# indoor-air-quality-shield.net
KiCad netlist of a schematic drawn in EAGLE
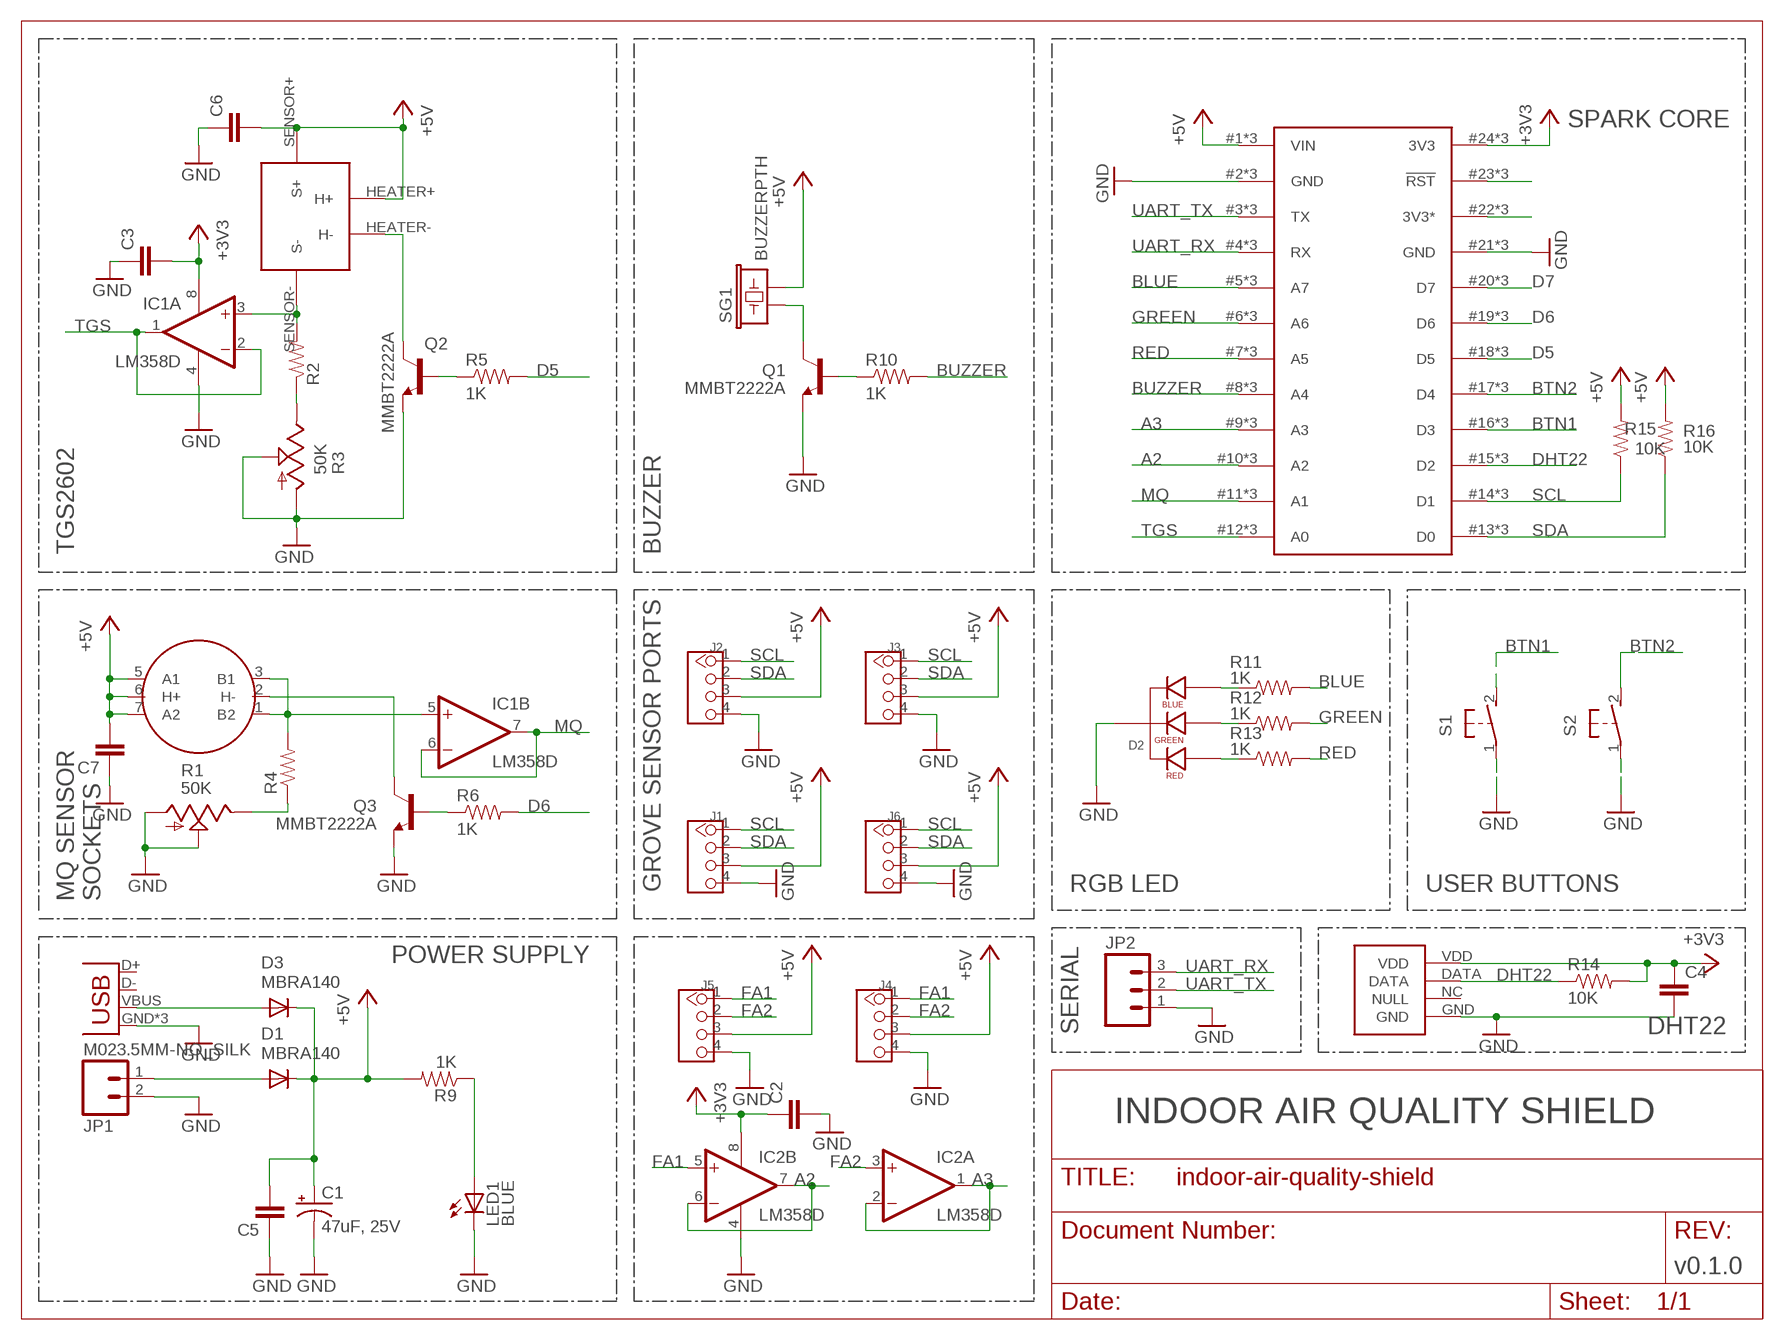
[diagram p0: schematic, sheet 1]

(export (version "E")
  (design (tool "Eeschema 10.0.6"))
  (components
    (comp (ref "C1")
      (value "47uF, 25V")
      (footprint "eagle-import:PANASONIC_D")
      (libsource (lib "eagle-import") (part "CAP_POLD"))
    )
    (comp (ref "C2")
      (value "C-EUC0603")
      (footprint "eagle-import:C0603")
      (libsource (lib "eagle-import") (part "C-EUC0603"))
    )
    (comp (ref "C3")
      (value "C-EUC0603")
      (footprint "eagle-import:C0603")
      (libsource (lib "eagle-import") (part "C-EUC0603"))
    )
    (comp (ref "C4")
      (value "C-EUC0603")
      (footprint "eagle-import:C0603")
      (libsource (lib "eagle-import") (part "C-EUC0603"))
    )
    (comp (ref "C5")
      (value "C-EUC0603")
      (footprint "eagle-import:C0603")
      (libsource (lib "eagle-import") (part "C-EUC0603"))
    )
    (comp (ref "C6")
      (value "C-EUC0603")
      (footprint "eagle-import:C0603")
      (libsource (lib "eagle-import") (part "C-EUC0603"))
    )
    (comp (ref "C7")
      (value "C-EUC0603")
      (footprint "eagle-import:C0603")
      (libsource (lib "eagle-import") (part "C-EUC0603"))
    )
    (comp (ref "D1")
      (value "MBRA140")
      (footprint "eagle-import:SMA-DIODE")
      (libsource (lib "eagle-import") (part "DIODESMA"))
    )
    (comp (ref "D2")
      (value "LED-RGB-CC-THRUCLEAR")
      (footprint "eagle-import:LED-RGB-THRU")
      (libsource (lib "eagle-import") (part "LED-RGB-CC-THRUCLEAR"))
    )
    (comp (ref "D3")
      (value "MBRA140")
      (footprint "eagle-import:SMA-DIODE")
      (libsource (lib "eagle-import") (part "DIODESMA"))
    )
    (comp (ref "IC1")
      (value "LM358D")
      (footprint "eagle-import:SO08")
      (libsource (lib "eagle-import") (part "LM358D"))
    )
    (comp (ref "IC2")
      (value "LM358D")
      (footprint "eagle-import:SO08")
      (libsource (lib "eagle-import") (part "LM358D"))
    )
    (comp (ref "J1")
      (value "TWIG-4P-2.0'D90'")
      (footprint "eagle-import:4P-2.0-90D-W_O-BUCKLE")
      (libsource (lib "eagle-import") (part "TWIG-4P-2.0'D90'"))
    )
    (comp (ref "J2")
      (value "TWIG-4P-2.0'D90'")
      (footprint "eagle-import:4P-2.0-90D-W_O-BUCKLE")
      (libsource (lib "eagle-import") (part "TWIG-4P-2.0'D90'"))
    )
    (comp (ref "J3")
      (value "TWIG-4P-2.0'D90'")
      (footprint "eagle-import:4P-2.0-90D-W_O-BUCKLE")
      (libsource (lib "eagle-import") (part "TWIG-4P-2.0'D90'"))
    )
    (comp (ref "J4")
      (value "TWIG-4P-2.0'D90'")
      (footprint "eagle-import:4P-2.0-90D-W_O-BUCKLE")
      (libsource (lib "eagle-import") (part "TWIG-4P-2.0'D90'"))
    )
    (comp (ref "J5")
      (value "TWIG-4P-2.0'D90'")
      (footprint "eagle-import:4P-2.0-90D-W_O-BUCKLE")
      (libsource (lib "eagle-import") (part "TWIG-4P-2.0'D90'"))
    )
    (comp (ref "J6")
      (value "TWIG-4P-2.0'D90'")
      (footprint "eagle-import:4P-2.0-90D-W_O-BUCKLE")
      (libsource (lib "eagle-import") (part "TWIG-4P-2.0'D90'"))
    )
    (comp (ref "JP1")
      (value "M023.5MM-NO_SILK")
      (footprint "eagle-import:SCREWTERMINAL-3.5MM-2-NS")
      (libsource (lib "eagle-import") (part "M023.5MM-NO_SILK"))
    )
    (comp (ref "JP2")
      (value "M03PTH")
      (footprint "eagle-import:1X03")
      (libsource (lib "eagle-import") (part "M03PTH"))
    )
    (comp (ref "JP3")
      (value "USBUSB-MICROB-SLOT-HOLE")
      (footprint "eagle-import:USB-MICROB-SLOT-HOLE")
      (libsource (lib "eagle-import") (part "USBUSB-MICROB-SLOT-HOLE"))
    )
    (comp (ref "LED1")
      (value "BLUE")
      (footprint "eagle-import:LED-0603")
      (libsource (lib "eagle-import") (part "LED0603"))
    )
    (comp (ref "Q1")
      (value "MMBT2222A")
      (footprint "eagle-import:SOT23-3")
      (libsource (lib "eagle-import") (part "TRANSISTOR_NPNMMBT2222A"))
    )
    (comp (ref "Q2")
      (value "MMBT2222A")
      (footprint "eagle-import:SOT23-3")
      (libsource (lib "eagle-import") (part "TRANSISTOR_NPNMMBT2222A"))
    )
    (comp (ref "Q3")
      (value "MMBT2222A")
      (footprint "eagle-import:SOT23-3")
      (libsource (lib "eagle-import") (part "TRANSISTOR_NPNMMBT2222A"))
    )
    (comp (ref "R1")
      (value "50K")
      (footprint "eagle-import:RJ9W")
      (libsource (lib "eagle-import") (part "TRIM_US-RJ9W"))
    )
    (comp (ref "R2")
      (value "RESISTOR0603")
      (footprint "eagle-import:0603-RES")
      (libsource (lib "eagle-import") (part "RESISTOR0603"))
    )
    (comp (ref "R3")
      (value "50K")
      (footprint "eagle-import:RJ9W")
      (libsource (lib "eagle-import") (part "TRIM_US-RJ9W"))
    )
    (comp (ref "R4")
      (value "RESISTOR0603")
      (footprint "eagle-import:0603-RES")
      (libsource (lib "eagle-import") (part "RESISTOR0603"))
    )
    (comp (ref "R5")
      (value "1K")
      (footprint "eagle-import:0603-RES")
      (libsource (lib "eagle-import") (part "RESISTOR0603-RES"))
    )
    (comp (ref "R6")
      (value "1K")
      (footprint "eagle-import:0603-RES")
      (libsource (lib "eagle-import") (part "RESISTOR0603-RES"))
    )
    (comp (ref "R9")
      (value "1K")
      (footprint "eagle-import:0603-RES")
      (libsource (lib "eagle-import") (part "RESISTOR0603-RES"))
    )
    (comp (ref "R10")
      (value "1K")
      (footprint "eagle-import:0603-RES")
      (libsource (lib "eagle-import") (part "RESISTOR0603-RES"))
    )
    (comp (ref "R11")
      (value "1K")
      (footprint "eagle-import:0603-RES")
      (libsource (lib "eagle-import") (part "RESISTOR0603-RES"))
    )
    (comp (ref "R12")
      (value "1K")
      (footprint "eagle-import:0603-RES")
      (libsource (lib "eagle-import") (part "RESISTOR0603-RES"))
    )
    (comp (ref "R13")
      (value "1K")
      (footprint "eagle-import:0603-RES")
      (libsource (lib "eagle-import") (part "RESISTOR0603-RES"))
    )
    (comp (ref "R14")
      (value "10K")
      (footprint "eagle-import:0603-RES")
      (libsource (lib "eagle-import") (part "RESISTOR0603-RES"))
    )
    (comp (ref "R15")
      (value "10K")
      (footprint "eagle-import:0603-RES")
      (libsource (lib "eagle-import") (part "RESISTOR0603-RES"))
    )
    (comp (ref "R16")
      (value "10K")
      (footprint "eagle-import:0603-RES")
      (libsource (lib "eagle-import") (part "RESISTOR0603-RES"))
    )
    (comp (ref "S1")
      (value "31-XX")
      (footprint "eagle-import:B3F-31XX")
      (fields (field (name "MPN") "B3F-3100"))
      (libsource (lib "eagle-import") (part "31-XX"))
    )
    (comp (ref "S2")
      (value "31-XX")
      (footprint "eagle-import:B3F-31XX")
      (fields (field (name "MPN") "B3F-3100"))
      (libsource (lib "eagle-import") (part "31-XX"))
    )
    (comp (ref "SG1")
      (value "BUZZERPTH")
      (footprint "eagle-import:BUZZER-12MM")
      (libsource (lib "eagle-import") (part "BUZZERPTH"))
    )
    (comp (ref "U$1")
      (value "TGS2602")
      (footprint "eagle-import:TGS2602")
      (libsource (lib "eagle-import") (part "TGS2602"))
    )
    (comp (ref "U$2")
      (value "MQ_SENSOR_SOCKET")
      (footprint "eagle-import:MQ_SENSOR_SOCKET")
      (libsource (lib "eagle-import") (part "MQ_SENSOR_SOCKET"))
    )
    (comp (ref "U$5")
      (value "DHT22")
      (footprint "eagle-import:DHT22")
      (libsource (lib "eagle-import") (part "DHT22"))
    )
    (comp (ref "U$6")
      (value "SPARK_CORE")
      (footprint "eagle-import:SPARK_CORE_STACKABLE")
      (libsource (lib "eagle-import") (part "SPARK_CORE"))
    )
  )
  (nets
    (net (code "1") (name "+3V3") (class "Default")
      (node (ref "C2") (pin "1") (pinfunction "1_1") (pintype "passive"))
      (node (ref "C3") (pin "2") (pinfunction "2_2") (pintype "passive"))
      (node (ref "C4") (pin "1") (pinfunction "1_1") (pintype "passive"))
      (node (ref "IC1") (pin "8") (pinfunction "V+_8") (pintype "power_in"))
      (node (ref "IC2") (pin "8") (pinfunction "V+_8") (pintype "power_in"))
      (node (ref "R14") (pin "2") (pinfunction "2_2") (pintype "passive"))
      (node (ref "U$5") (pin "VDD") (pinfunction "VDD_VDD") (pintype "power_in"))
      (node (ref "U$6") (pin "#24") (pinfunction "3V3_#24") (pintype "power_in"))
      (node (ref "U$6") (pin "24") (pinfunction "3V3_24") (pintype "power_in"))
      (node (ref "U$6") (pin "@24") (pinfunction "3V3_@24") (pintype "power_in"))
    )
    (net (code "2") (name "+5V") (class "Default")
      (node (ref "C1") (pin "+") (pinfunction "+_+") (pintype "passive"))
      (node (ref "C5") (pin "2") (pinfunction "2_2") (pintype "passive"))
      (node (ref "C6") (pin "2") (pinfunction "2_2") (pintype "passive"))
      (node (ref "C7") (pin "2") (pinfunction "2_2") (pintype "passive"))
      (node (ref "D1") (pin "C") (pinfunction "C_C") (pintype "passive"))
      (node (ref "D3") (pin "C") (pinfunction "C_C") (pintype "passive"))
      (node (ref "J1") (pin "3") (pinfunction "3_3") (pintype "bidirectional"))
      (node (ref "J2") (pin "3") (pinfunction "3_3") (pintype "bidirectional"))
      (node (ref "J3") (pin "3") (pinfunction "3_3") (pintype "bidirectional"))
      (node (ref "J4") (pin "3") (pinfunction "3_3") (pintype "bidirectional"))
      (node (ref "J5") (pin "3") (pinfunction "3_3") (pintype "bidirectional"))
      (node (ref "J6") (pin "3") (pinfunction "3_3") (pintype "bidirectional"))
      (node (ref "R15") (pin "2") (pinfunction "2_2") (pintype "passive"))
      (node (ref "R16") (pin "2") (pinfunction "2_2") (pintype "passive"))
      (node (ref "R9") (pin "2") (pinfunction "2_2") (pintype "passive"))
      (node (ref "SG1") (pin "-") (pinfunction "2_-") (pintype "passive"))
      (node (ref "U$1") (pin "HEATER+") (pinfunction "H+_HEATER+") (pintype "bidirectional"))
      (node (ref "U$1") (pin "SENSOR+") (pinfunction "S+_SENSOR+") (pintype "bidirectional"))
      (node (ref "U$2") (pin "5") (pinfunction "A1_5") (pintype "bidirectional"))
      (node (ref "U$2") (pin "6") (pinfunction "H+_6") (pintype "bidirectional"))
      (node (ref "U$2") (pin "7") (pinfunction "A2_7") (pintype "bidirectional"))
      (node (ref "U$6") (pin "#1") (pinfunction "VIN_#1") (pintype "power_in"))
      (node (ref "U$6") (pin "1") (pinfunction "VIN_1") (pintype "power_in"))
      (node (ref "U$6") (pin "@1") (pinfunction "VIN_@1") (pintype "power_in"))
    )
    (net (code "3") (name "/A2") (class "Default")
      (node (ref "IC2") (pin "6") (pinfunction "-IN_6") (pintype "input"))
      (node (ref "IC2") (pin "7") (pinfunction "OUT_7") (pintype "output"))
      (node (ref "U$6") (pin "#10") (pinfunction "A2_#10") (pintype "bidirectional"))
      (node (ref "U$6") (pin "10") (pinfunction "A2_10") (pintype "bidirectional"))
      (node (ref "U$6") (pin "@10") (pinfunction "A2_@10") (pintype "bidirectional"))
    )
    (net (code "4") (name "/A3") (class "Default")
      (node (ref "IC2") (pin "1") (pinfunction "OUT_1") (pintype "output"))
      (node (ref "IC2") (pin "2") (pinfunction "-IN_2") (pintype "input"))
      (node (ref "U$6") (pin "#9") (pinfunction "A3_#9") (pintype "bidirectional"))
      (node (ref "U$6") (pin "9") (pinfunction "A3_9") (pintype "bidirectional"))
      (node (ref "U$6") (pin "@9") (pinfunction "A3_@9") (pintype "bidirectional"))
    )
    (net (code "5") (name "/BLUE") (class "Default")
      (node (ref "R11") (pin "2") (pinfunction "2_2") (pintype "passive"))
      (node (ref "U$6") (pin "#5") (pinfunction "A7_#5") (pintype "bidirectional"))
      (node (ref "U$6") (pin "5") (pinfunction "A7_5") (pintype "bidirectional"))
      (node (ref "U$6") (pin "@5") (pinfunction "A7_@5") (pintype "bidirectional"))
    )
    (net (code "6") (name "/BTN1") (class "Default")
      (node (ref "S1") (pin "2") (pinfunction "S_2") (pintype "passive"))
      (node (ref "U$6") (pin "#16") (pinfunction "D3_#16") (pintype "bidirectional"))
      (node (ref "U$6") (pin "16") (pinfunction "D3_16") (pintype "bidirectional"))
      (node (ref "U$6") (pin "@16") (pinfunction "D3_@16") (pintype "bidirectional"))
    )
    (net (code "7") (name "/BTN2") (class "Default")
      (node (ref "S2") (pin "2") (pinfunction "S_2") (pintype "passive"))
      (node (ref "U$6") (pin "#17") (pinfunction "D4_#17") (pintype "bidirectional"))
      (node (ref "U$6") (pin "17") (pinfunction "D4_17") (pintype "bidirectional"))
      (node (ref "U$6") (pin "@17") (pinfunction "D4_@17") (pintype "bidirectional"))
    )
    (net (code "8") (name "/BUZZER") (class "Default")
      (node (ref "R10") (pin "2") (pinfunction "2_2") (pintype "passive"))
      (node (ref "U$6") (pin "#8") (pinfunction "A4_#8") (pintype "bidirectional"))
      (node (ref "U$6") (pin "8") (pinfunction "A4_8") (pintype "bidirectional"))
      (node (ref "U$6") (pin "@8") (pinfunction "A4_@8") (pintype "bidirectional"))
    )
    (net (code "9") (name "/D5") (class "Default")
      (node (ref "R5") (pin "2") (pinfunction "2_2") (pintype "passive"))
      (node (ref "U$6") (pin "#18") (pinfunction "D5_#18") (pintype "bidirectional"))
      (node (ref "U$6") (pin "18") (pinfunction "D5_18") (pintype "bidirectional"))
      (node (ref "U$6") (pin "@18") (pinfunction "D5_@18") (pintype "bidirectional"))
    )
    (net (code "10") (name "/D6") (class "Default")
      (node (ref "R6") (pin "2") (pinfunction "2_2") (pintype "passive"))
      (node (ref "U$6") (pin "#19") (pinfunction "D6_#19") (pintype "bidirectional"))
      (node (ref "U$6") (pin "19") (pinfunction "D6_19") (pintype "bidirectional"))
      (node (ref "U$6") (pin "@19") (pinfunction "D6_@19") (pintype "bidirectional"))
    )
    (net (code "11") (name "/D7") (class "Default")
      (node (ref "U$6") (pin "#20") (pinfunction "D7_#20") (pintype "bidirectional"))
      (node (ref "U$6") (pin "20") (pinfunction "D7_20") (pintype "bidirectional"))
      (node (ref "U$6") (pin "@20") (pinfunction "D7_@20") (pintype "bidirectional"))
    )
    (net (code "12") (name "/DHT22") (class "Default")
      (node (ref "R14") (pin "1") (pinfunction "1_1") (pintype "passive"))
      (node (ref "U$5") (pin "DATA") (pinfunction "DATA_DATA") (pintype "output"))
      (node (ref "U$6") (pin "#15") (pinfunction "D2_#15") (pintype "bidirectional"))
      (node (ref "U$6") (pin "15") (pinfunction "D2_15") (pintype "bidirectional"))
      (node (ref "U$6") (pin "@15") (pinfunction "D2_@15") (pintype "bidirectional"))
    )
    (net (code "13") (name "/FA1") (class "Default")
      (node (ref "IC2") (pin "5") (pinfunction "+IN_5") (pintype "input"))
      (node (ref "J4") (pin "1") (pinfunction "1_1") (pintype "bidirectional"))
      (node (ref "J5") (pin "1") (pinfunction "1_1") (pintype "bidirectional"))
    )
    (net (code "14") (name "/FA2") (class "Default")
      (node (ref "IC2") (pin "3") (pinfunction "+IN_3") (pintype "input"))
      (node (ref "J4") (pin "2") (pinfunction "2_2") (pintype "bidirectional"))
      (node (ref "J5") (pin "2") (pinfunction "2_2") (pintype "bidirectional"))
    )
    (net (code "15") (name "/GREEN") (class "Default")
      (node (ref "R12") (pin "2") (pinfunction "2_2") (pintype "passive"))
      (node (ref "U$6") (pin "#6") (pinfunction "A6_#6") (pintype "bidirectional"))
      (node (ref "U$6") (pin "6") (pinfunction "A6_6") (pintype "bidirectional"))
      (node (ref "U$6") (pin "@6") (pinfunction "A6_@6") (pintype "bidirectional"))
    )
    (net (code "16") (name "/MQ") (class "Default")
      (node (ref "IC1") (pin "6") (pinfunction "-IN_6") (pintype "input"))
      (node (ref "IC1") (pin "7") (pinfunction "OUT_7") (pintype "output"))
      (node (ref "U$6") (pin "#11") (pinfunction "A1_#11") (pintype "bidirectional"))
      (node (ref "U$6") (pin "11") (pinfunction "A1_11") (pintype "bidirectional"))
      (node (ref "U$6") (pin "@11") (pinfunction "A1_@11") (pintype "bidirectional"))
    )
    (net (code "17") (name "/RED") (class "Default")
      (node (ref "R13") (pin "2") (pinfunction "2_2") (pintype "passive"))
      (node (ref "U$6") (pin "#7") (pinfunction "A5_#7") (pintype "bidirectional"))
      (node (ref "U$6") (pin "7") (pinfunction "A5_7") (pintype "bidirectional"))
      (node (ref "U$6") (pin "@7") (pinfunction "A5_@7") (pintype "bidirectional"))
    )
    (net (code "18") (name "/SCL") (class "Default")
      (node (ref "J1") (pin "1") (pinfunction "1_1") (pintype "bidirectional"))
      (node (ref "J2") (pin "1") (pinfunction "1_1") (pintype "bidirectional"))
      (node (ref "J3") (pin "1") (pinfunction "1_1") (pintype "bidirectional"))
      (node (ref "J6") (pin "1") (pinfunction "1_1") (pintype "bidirectional"))
      (node (ref "R15") (pin "1") (pinfunction "1_1") (pintype "passive"))
      (node (ref "U$6") (pin "#14") (pinfunction "D1_#14") (pintype "bidirectional"))
      (node (ref "U$6") (pin "14") (pinfunction "D1_14") (pintype "bidirectional"))
      (node (ref "U$6") (pin "@14") (pinfunction "D1_@14") (pintype "bidirectional"))
    )
    (net (code "19") (name "/SDA") (class "Default")
      (node (ref "J1") (pin "2") (pinfunction "2_2") (pintype "bidirectional"))
      (node (ref "J2") (pin "2") (pinfunction "2_2") (pintype "bidirectional"))
      (node (ref "J3") (pin "2") (pinfunction "2_2") (pintype "bidirectional"))
      (node (ref "J6") (pin "2") (pinfunction "2_2") (pintype "bidirectional"))
      (node (ref "R16") (pin "1") (pinfunction "1_1") (pintype "passive"))
      (node (ref "U$6") (pin "#13") (pinfunction "D0_#13") (pintype "bidirectional"))
      (node (ref "U$6") (pin "13") (pinfunction "D0_13") (pintype "bidirectional"))
      (node (ref "U$6") (pin "@13") (pinfunction "D0_@13") (pintype "bidirectional"))
    )
    (net (code "20") (name "/TGS") (class "Default")
      (node (ref "IC1") (pin "1") (pinfunction "OUT_1") (pintype "output"))
      (node (ref "IC1") (pin "2") (pinfunction "-IN_2") (pintype "input"))
      (node (ref "U$6") (pin "#12") (pinfunction "A0_#12") (pintype "bidirectional"))
      (node (ref "U$6") (pin "12") (pinfunction "A0_12") (pintype "bidirectional"))
      (node (ref "U$6") (pin "@12") (pinfunction "A0_@12") (pintype "bidirectional"))
    )
    (net (code "21") (name "/UART_RX") (class "Default")
      (node (ref "JP2") (pin "3") (pinfunction "3_3") (pintype "passive"))
      (node (ref "U$6") (pin "#4") (pinfunction "RX_#4") (pintype "bidirectional"))
      (node (ref "U$6") (pin "4") (pinfunction "RX_4") (pintype "bidirectional"))
      (node (ref "U$6") (pin "@4") (pinfunction "RX_@4") (pintype "bidirectional"))
    )
    (net (code "22") (name "/UART_TX") (class "Default")
      (node (ref "JP2") (pin "2") (pinfunction "2_2") (pintype "passive"))
      (node (ref "U$6") (pin "#3") (pinfunction "TX_#3") (pintype "bidirectional"))
      (node (ref "U$6") (pin "3") (pinfunction "TX_3") (pintype "bidirectional"))
      (node (ref "U$6") (pin "@3") (pinfunction "TX_@3") (pintype "bidirectional"))
    )
    (net (code "23") (name "GND") (class "Default")
      (node (ref "C1") (pin "-") (pinfunction "-_-") (pintype "passive"))
      (node (ref "C2") (pin "2") (pinfunction "2_2") (pintype "passive"))
      (node (ref "C3") (pin "1") (pinfunction "1_1") (pintype "passive"))
      (node (ref "C4") (pin "2") (pinfunction "2_2") (pintype "passive"))
      (node (ref "C5") (pin "1") (pinfunction "1_1") (pintype "passive"))
      (node (ref "C6") (pin "1") (pinfunction "1_1") (pintype "passive"))
      (node (ref "C7") (pin "1") (pinfunction "1_1") (pintype "passive"))
      (node (ref "D2") (pin "2") (pinfunction "CATHODE_2") (pintype "bidirectional"))
      (node (ref "IC1") (pin "4") (pinfunction "V-_4") (pintype "power_in"))
      (node (ref "IC2") (pin "4") (pinfunction "V-_4") (pintype "power_in"))
      (node (ref "J1") (pin "4") (pinfunction "4_4") (pintype "bidirectional"))
      (node (ref "J2") (pin "4") (pinfunction "4_4") (pintype "bidirectional"))
      (node (ref "J3") (pin "4") (pinfunction "4_4") (pintype "bidirectional"))
      (node (ref "J4") (pin "4") (pinfunction "4_4") (pintype "bidirectional"))
      (node (ref "J5") (pin "4") (pinfunction "4_4") (pintype "bidirectional"))
      (node (ref "J6") (pin "4") (pinfunction "4_4") (pintype "bidirectional"))
      (node (ref "JP1") (pin "2") (pinfunction "2_2") (pintype "passive"))
      (node (ref "JP2") (pin "1") (pinfunction "1_1") (pintype "passive"))
      (node (ref "JP3") (pin "GND") (pinfunction "GND_GND") (pintype "bidirectional"))
      (node (ref "JP3") (pin "MT1") (pinfunction "GND_MT1") (pintype "bidirectional"))
      (node (ref "JP3") (pin "MT2") (pinfunction "GND_MT2") (pintype "bidirectional"))
      (node (ref "LED1") (pin "C") (pinfunction "C_C") (pintype "passive"))
      (node (ref "Q1") (pin "2") (pinfunction "E_2") (pintype "passive"))
      (node (ref "Q2") (pin "2") (pinfunction "E_2") (pintype "passive"))
      (node (ref "Q3") (pin "2") (pinfunction "E_2") (pintype "passive"))
      (node (ref "R1") (pin "A") (pinfunction "A_A") (pintype "passive"))
      (node (ref "R1") (pin "S") (pinfunction "S_S") (pintype "passive"))
      (node (ref "R3") (pin "A") (pinfunction "A_A") (pintype "passive"))
      (node (ref "R3") (pin "S") (pinfunction "S_S") (pintype "passive"))
      (node (ref "S1") (pin "1") (pinfunction "P_1") (pintype "passive"))
      (node (ref "S2") (pin "1") (pinfunction "P_1") (pintype "passive"))
      (node (ref "U$5") (pin "GND") (pinfunction "GND_GND") (pintype "power_in"))
      (node (ref "U$6") (pin "#2") (pinfunction "GND_#2") (pintype "power_in"))
      (node (ref "U$6") (pin "#21") (pinfunction "GND_#21") (pintype "power_in"))
      (node (ref "U$6") (pin "2") (pinfunction "GND_2") (pintype "power_in"))
      (node (ref "U$6") (pin "21") (pinfunction "GND_21") (pintype "power_in"))
      (node (ref "U$6") (pin "@2") (pinfunction "GND_@2") (pintype "power_in"))
      (node (ref "U$6") (pin "@21") (pinfunction "GND_@21") (pintype "power_in"))
    )
    (net (code "24") (name "Net-(D1-PadA)") (class "Default")
      (node (ref "D1") (pin "A") (pinfunction "A_A") (pintype "passive"))
      (node (ref "JP1") (pin "1") (pinfunction "1_1") (pintype "passive"))
    )
    (net (code "25") (name "Net-(D2-BLUE_CATHODE)") (class "Default")
      (node (ref "D2") (pin "4") (pinfunction "BLUE_CATHODE_4") (pintype "bidirectional"))
      (node (ref "R11") (pin "1") (pinfunction "1_1") (pintype "passive"))
    )
    (net (code "26") (name "Net-(D2-GREEN_CATHODE)") (class "Default")
      (node (ref "D2") (pin "3") (pinfunction "GREEN_CATHODE_3") (pintype "bidirectional"))
      (node (ref "R12") (pin "1") (pinfunction "1_1") (pintype "passive"))
    )
    (net (code "27") (name "Net-(D2-RED_CATHODE)") (class "Default")
      (node (ref "D2") (pin "1") (pinfunction "RED_CATHODE_1") (pintype "bidirectional"))
      (node (ref "R13") (pin "1") (pinfunction "1_1") (pintype "passive"))
    )
    (net (code "28") (name "Net-(D3-PadA)") (class "Default")
      (node (ref "D3") (pin "A") (pinfunction "A_A") (pintype "passive"))
      (node (ref "JP3") (pin "VBUS") (pinfunction "VBUS_VBUS") (pintype "bidirectional"))
    )
    (net (code "29") (name "Net-(IC1A-+IN)") (class "Default")
      (node (ref "IC1") (pin "3") (pinfunction "+IN_3") (pintype "input"))
      (node (ref "R2") (pin "2") (pinfunction "2_2") (pintype "passive"))
      (node (ref "U$1") (pin "SENSOR-") (pinfunction "S-_SENSOR-") (pintype "bidirectional"))
    )
    (net (code "30") (name "Net-(IC1B-+IN)") (class "Default")
      (node (ref "IC1") (pin "5") (pinfunction "+IN_5") (pintype "input"))
      (node (ref "R4") (pin "2") (pinfunction "2_2") (pintype "passive"))
      (node (ref "U$2") (pin "1") (pinfunction "B2_1") (pintype "bidirectional"))
      (node (ref "U$2") (pin "3") (pinfunction "B1_3") (pintype "bidirectional"))
    )
    (net (code "31") (name "Net-(LED1-PadA)") (class "Default")
      (node (ref "LED1") (pin "A") (pinfunction "A_A") (pintype "passive"))
      (node (ref "R9") (pin "1") (pinfunction "1_1") (pintype "passive"))
    )
    (net (code "32") (name "Net-(Q1-B)") (class "Default")
      (node (ref "Q1") (pin "1") (pinfunction "B_1") (pintype "passive"))
      (node (ref "R10") (pin "1") (pinfunction "1_1") (pintype "passive"))
    )
    (net (code "33") (name "Net-(Q1-C)") (class "Default")
      (node (ref "Q1") (pin "3") (pinfunction "C_3") (pintype "passive"))
      (node (ref "SG1") (pin "+") (pinfunction "1_+") (pintype "passive"))
    )
    (net (code "34") (name "Net-(Q2-B)") (class "Default")
      (node (ref "Q2") (pin "1") (pinfunction "B_1") (pintype "passive"))
      (node (ref "R5") (pin "1") (pinfunction "1_1") (pintype "passive"))
    )
    (net (code "35") (name "Net-(Q2-C)") (class "Default")
      (node (ref "Q2") (pin "3") (pinfunction "C_3") (pintype "passive"))
      (node (ref "U$1") (pin "HEATER-") (pinfunction "H-_HEATER-") (pintype "bidirectional"))
    )
    (net (code "36") (name "Net-(Q3-B)") (class "Default")
      (node (ref "Q3") (pin "1") (pinfunction "B_1") (pintype "passive"))
      (node (ref "R6") (pin "1") (pinfunction "1_1") (pintype "passive"))
    )
    (net (code "37") (name "Net-(Q3-C)") (class "Default")
      (node (ref "Q3") (pin "3") (pinfunction "C_3") (pintype "passive"))
      (node (ref "U$2") (pin "2") (pinfunction "H-_2") (pintype "bidirectional"))
    )
    (net (code "38") (name "Net-(R1-PadE)") (class "Default")
      (node (ref "R1") (pin "E") (pinfunction "E_E") (pintype "passive"))
      (node (ref "R4") (pin "1") (pinfunction "1_1") (pintype "passive"))
    )
    (net (code "39") (name "Net-(R2-Pad1)") (class "Default")
      (node (ref "R2") (pin "1") (pinfunction "1_1") (pintype "passive"))
      (node (ref "R3") (pin "E") (pinfunction "E_E") (pintype "passive"))
    )
    (net (code "40") (name "Net-(U$6-3V3*-Pad#22)") (class "Default")
      (node (ref "U$6") (pin "#22") (pinfunction "3V3*_#22") (pintype "power_in"))
      (node (ref "U$6") (pin "22") (pinfunction "3V3*_22") (pintype "power_in"))
      (node (ref "U$6") (pin "@22") (pinfunction "3V3*_@22") (pintype "power_in"))
    )
    (net (code "41") (name "Net-(U$6-~{RST}-Pad#23)") (class "Default")
      (node (ref "U$6") (pin "#23") (pinfunction "~{RST}_#23") (pintype "bidirectional"))
      (node (ref "U$6") (pin "23") (pinfunction "~{RST}_23") (pintype "bidirectional"))
      (node (ref "U$6") (pin "@23") (pinfunction "~{RST}_@23") (pintype "bidirectional"))
    )
    (net (code "42") (name "unconnected-(JP3-PadD+)") (class "Default")
      (node (ref "JP3") (pin "D+") (pinfunction "D+_D+") (pintype "bidirectional"))
    )
    (net (code "43") (name "unconnected-(JP3-PadD-)") (class "Default")
      (node (ref "JP3") (pin "D-") (pinfunction "D-_D-") (pintype "bidirectional"))
    )
    (net (code "44") (name "unconnected-(U$5-NULL-PadNC)") (class "Default")
      (node (ref "U$5") (pin "NC") (pinfunction "NULL_NC") (pintype "no_connect"))
    )
  )
)
